# DRV8874_motor_driver.net
KiCad netlist of a schematic drawn in Altium Designer
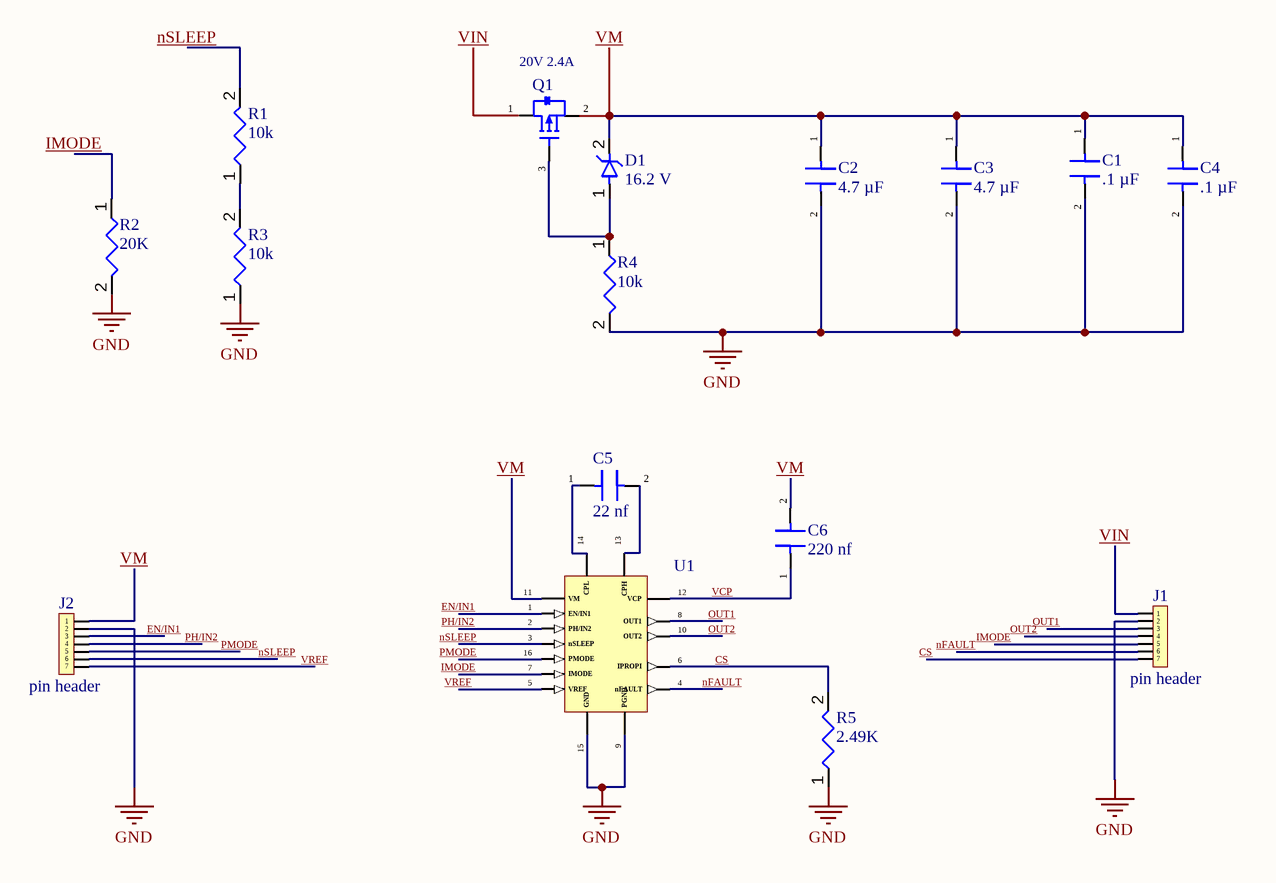
[diagram p0: DRV8874 motor driver.SchDoc]

(export (version "E")
  (design (tool "Eeschema 10.0.6"))
  (components
    (comp (ref "C1")
      (value ".1 µF")
      (footprint "CAP SMD")
      (description "22 µF ±20% 6.3V Ceramic Capacitor X5R 0603 (1608 Metric)")
      (libsource (lib "integraed library phase2") (part "capacitor smd"))
    )
    (comp (ref "C2")
      (value "4.7 µF")
      (footprint "CAP SMD")
      (description "22 µF ±20% 6.3V Ceramic Capacitor X5R 0603 (1608 Metric)")
      (libsource (lib "integraed library phase2") (part "capacitor smd"))
    )
    (comp (ref "C3")
      (value "4.7 µF")
      (footprint "CAP SMD")
      (description "22 µF ±20% 6.3V Ceramic Capacitor X5R 0603 (1608 Metric)")
      (libsource (lib "integraed library phase2") (part "capacitor smd"))
    )
    (comp (ref "C4")
      (value ".1 µF")
      (footprint "CAP SMD")
      (description "22 µF ±20% 6.3V Ceramic Capacitor X5R 0603 (1608 Metric)")
      (libsource (lib "integraed library phase2") (part "capacitor smd"))
    )
    (comp (ref "C5")
      (value "22 nf")
      (footprint "CAP SMD")
      (description "22 µF ±20% 6.3V Ceramic Capacitor X5R 0603 (1608 Metric)")
      (libsource (lib "integraed library phase2") (part "capacitor smd"))
    )
    (comp (ref "C6")
      (value "220 nf")
      (footprint "CAP SMD")
      (description "22 µF ±20% 6.3V Ceramic Capacitor X5R 0603 (1608 Metric)")
      (libsource (lib "integraed library phase2") (part "capacitor smd"))
    )
    (comp (ref "D1")
      (value "16.2 V")
      (footprint "CAPCP2512X10N")
      (description "Zener Diode 16.2 V 300 mW Surface Mount SOD-323")
      (libsource (lib "integraed library phase2") (part "Zener Diode 16.2 V"))
    )
    (comp (ref "J1")
      (value "pin header")
      (footprint "pin header male - duplicate1")
      (libsource (lib "integraed library phase2") (part "pin header 7 positions"))
    )
    (comp (ref "J2")
      (value "pin header")
      (footprint "pin header male - duplicate1")
      (libsource (lib "") (part "pin header 7 positions_1"))
    )
    (comp (ref "Q1")
      (value "20V 2.4A")
      (footprint "SOTFL95P251X112-3N")
      (description "P-Channel 20 V 2.4A (Ta) 500mW (Ta) Surface Mount SOT-23-3")
      (libsource (lib "integraed library phase2") (part "MOSFET P-CH"))
    )
    (comp (ref "R1")
      (value "10k")
      (footprint "SMD RESISTOR")
      (libsource (lib "integraed library phase2") (part "resistor smd"))
    )
    (comp (ref "R2")
      (value "20K")
      (footprint "SMD RESISTOR")
      (libsource (lib "integraed library phase2") (part "resistor smd"))
    )
    (comp (ref "R3")
      (value "10k")
      (footprint "SMD RESISTOR")
      (libsource (lib "integraed library phase2") (part "resistor smd"))
    )
    (comp (ref "R4")
      (value "10k")
      (footprint "SMD RESISTOR")
      (libsource (lib "integraed library phase2") (part "resistor smd"))
    )
    (comp (ref "R5")
      (value "2.49K")
      (footprint "SMD RESISTOR")
      (libsource (lib "integraed library phase2") (part "resistor smd"))
    )
    (comp (ref "U1")
      (value "https://www.digikey.com/en/products/base-product/texas-instruments/296/DRV8874/21713")
      (footprint "TSOP65P640X120_HS-17N")
      (description "DRV8874 H-BRIDGE MOTOR DRIVER")
      (libsource (lib "integrated schmatic library phase2") (part "DRV8874 motor driver"))
    )
  )
  (nets
    (net (code "1") (name "/CS") (class "Default")
      (node (ref "J1") (pin "7") (pinfunction "7_7") (pintype "power_in"))
      (node (ref "R5") (pin "2") (pintype "passive"))
      (node (ref "U1") (pin "6") (pinfunction "IPROPI_6") (pintype "output"))
    )
    (net (code "2") (name "/EN{slash}IN1") (class "Default")
      (node (ref "J2") (pin "3") (pinfunction "3_3") (pintype "power_in"))
      (node (ref "U1") (pin "1") (pinfunction "EN/IN1_1") (pintype "input"))
    )
    (net (code "3") (name "/IMODE") (class "Default")
      (node (ref "J1") (pin "5") (pinfunction "5_5") (pintype "power_in"))
      (node (ref "R2") (pin "1") (pintype "passive"))
      (node (ref "U1") (pin "7") (pinfunction "IMODE_7") (pintype "input"))
    )
    (net (code "4") (name "/OUT1") (class "Default")
      (node (ref "J1") (pin "3") (pinfunction "3_3") (pintype "power_in"))
      (node (ref "U1") (pin "8") (pinfunction "OUT1_8") (pintype "output"))
    )
    (net (code "5") (name "/OUT2") (class "Default")
      (node (ref "J1") (pin "4") (pinfunction "4_4") (pintype "power_in"))
      (node (ref "U1") (pin "10") (pinfunction "OUT2_10") (pintype "output"))
    )
    (net (code "6") (name "/PH{slash}IN2") (class "Default")
      (node (ref "J2") (pin "4") (pinfunction "4_4") (pintype "power_in"))
      (node (ref "U1") (pin "2") (pinfunction "PH/IN2_2") (pintype "input"))
    )
    (net (code "7") (name "/PMODE") (class "Default")
      (node (ref "J2") (pin "5") (pinfunction "5_5") (pintype "power_in"))
      (node (ref "U1") (pin "16") (pinfunction "PMODE_16") (pintype "input"))
    )
    (net (code "8") (name "/VCP") (class "Default")
      (node (ref "C6") (pin "1") (pinfunction "1_1") (pintype "passive"))
      (node (ref "U1") (pin "12") (pinfunction "VCP_12") (pintype "power_in"))
    )
    (net (code "9") (name "/VIN") (class "Default")
      (node (ref "J1") (pin "1") (pinfunction "1_1") (pintype "power_in"))
      (node (ref "Q1") (pin "1") (pinfunction "1_1") (pintype "passive"))
    )
    (net (code "10") (name "/VM") (class "Default")
      (node (ref "C1") (pin "1") (pinfunction "1_1") (pintype "passive"))
      (node (ref "C2") (pin "1") (pinfunction "1_1") (pintype "passive"))
      (node (ref "C3") (pin "1") (pinfunction "1_1") (pintype "passive"))
      (node (ref "C4") (pin "1") (pinfunction "1_1") (pintype "passive"))
      (node (ref "C6") (pin "2") (pinfunction "2_2") (pintype "passive"))
      (node (ref "D1") (pin "2") (pinfunction "2_2") (pintype "passive"))
      (node (ref "J2") (pin "1") (pinfunction "1_1") (pintype "power_in"))
      (node (ref "Q1") (pin "2") (pinfunction "2_2") (pintype "passive"))
      (node (ref "U1") (pin "11") (pinfunction "VM_11") (pintype "power_in"))
    )
    (net (code "11") (name "/VREF") (class "Default")
      (node (ref "J2") (pin "7") (pinfunction "7_7") (pintype "power_in"))
      (node (ref "U1") (pin "5") (pinfunction "VREF_5") (pintype "input"))
    )
    (net (code "12") (name "/nFAULT") (class "Default")
      (node (ref "J1") (pin "6") (pinfunction "6_6") (pintype "power_in"))
      (node (ref "U1") (pin "4") (pinfunction "nFAULT_4") (pintype "output"))
    )
    (net (code "13") (name "/nSLEEP") (class "Default")
      (node (ref "J2") (pin "6") (pinfunction "6_6") (pintype "power_in"))
      (node (ref "R1") (pin "2") (pintype "passive"))
      (node (ref "U1") (pin "3") (pinfunction "nSLEEP_3") (pintype "input"))
    )
    (net (code "14") (name "GND") (class "Default")
      (node (ref "C1") (pin "2") (pinfunction "2_2") (pintype "passive"))
      (node (ref "C2") (pin "2") (pinfunction "2_2") (pintype "passive"))
      (node (ref "C3") (pin "2") (pinfunction "2_2") (pintype "passive"))
      (node (ref "C4") (pin "2") (pinfunction "2_2") (pintype "passive"))
      (node (ref "J1") (pin "2") (pinfunction "2_2") (pintype "power_in"))
      (node (ref "J2") (pin "2") (pinfunction "2_2") (pintype "power_in"))
      (node (ref "R2") (pin "2") (pintype "passive"))
      (node (ref "R3") (pin "1") (pintype "passive"))
      (node (ref "R4") (pin "2") (pintype "passive"))
      (node (ref "R5") (pin "1") (pintype "passive"))
      (node (ref "U1") (pin "15") (pinfunction "GND_15") (pintype "power_in"))
      (node (ref "U1") (pin "9") (pinfunction "PGND_9") (pintype "power_in"))
    )
    (net (code "15") (name "Net-(D1-Pad1)") (class "Default")
      (node (ref "D1") (pin "1") (pinfunction "1_1") (pintype "passive"))
      (node (ref "Q1") (pin "3") (pinfunction "3_3") (pintype "passive"))
      (node (ref "R4") (pin "1") (pintype "passive"))
    )
    (net (code "16") (name "Net-(R1-Pad1)") (class "Default")
      (node (ref "R1") (pin "1") (pintype "passive"))
      (node (ref "R3") (pin "2") (pintype "passive"))
    )
    (net (code "17") (name "Net-(U1-CPH)") (class "Default")
      (node (ref "C5") (pin "2") (pinfunction "2_2") (pintype "passive"))
      (node (ref "U1") (pin "13") (pinfunction "CPH_13") (pintype "power_in"))
    )
    (net (code "18") (name "Net-(U1-CPL)") (class "Default")
      (node (ref "C5") (pin "1") (pinfunction "1_1") (pintype "passive"))
      (node (ref "U1") (pin "14") (pinfunction "CPL_14") (pintype "power_in"))
    )
  )
)
